# PandaBoard_Shell.net
KiCad netlist of a schematic drawn in EAGLE
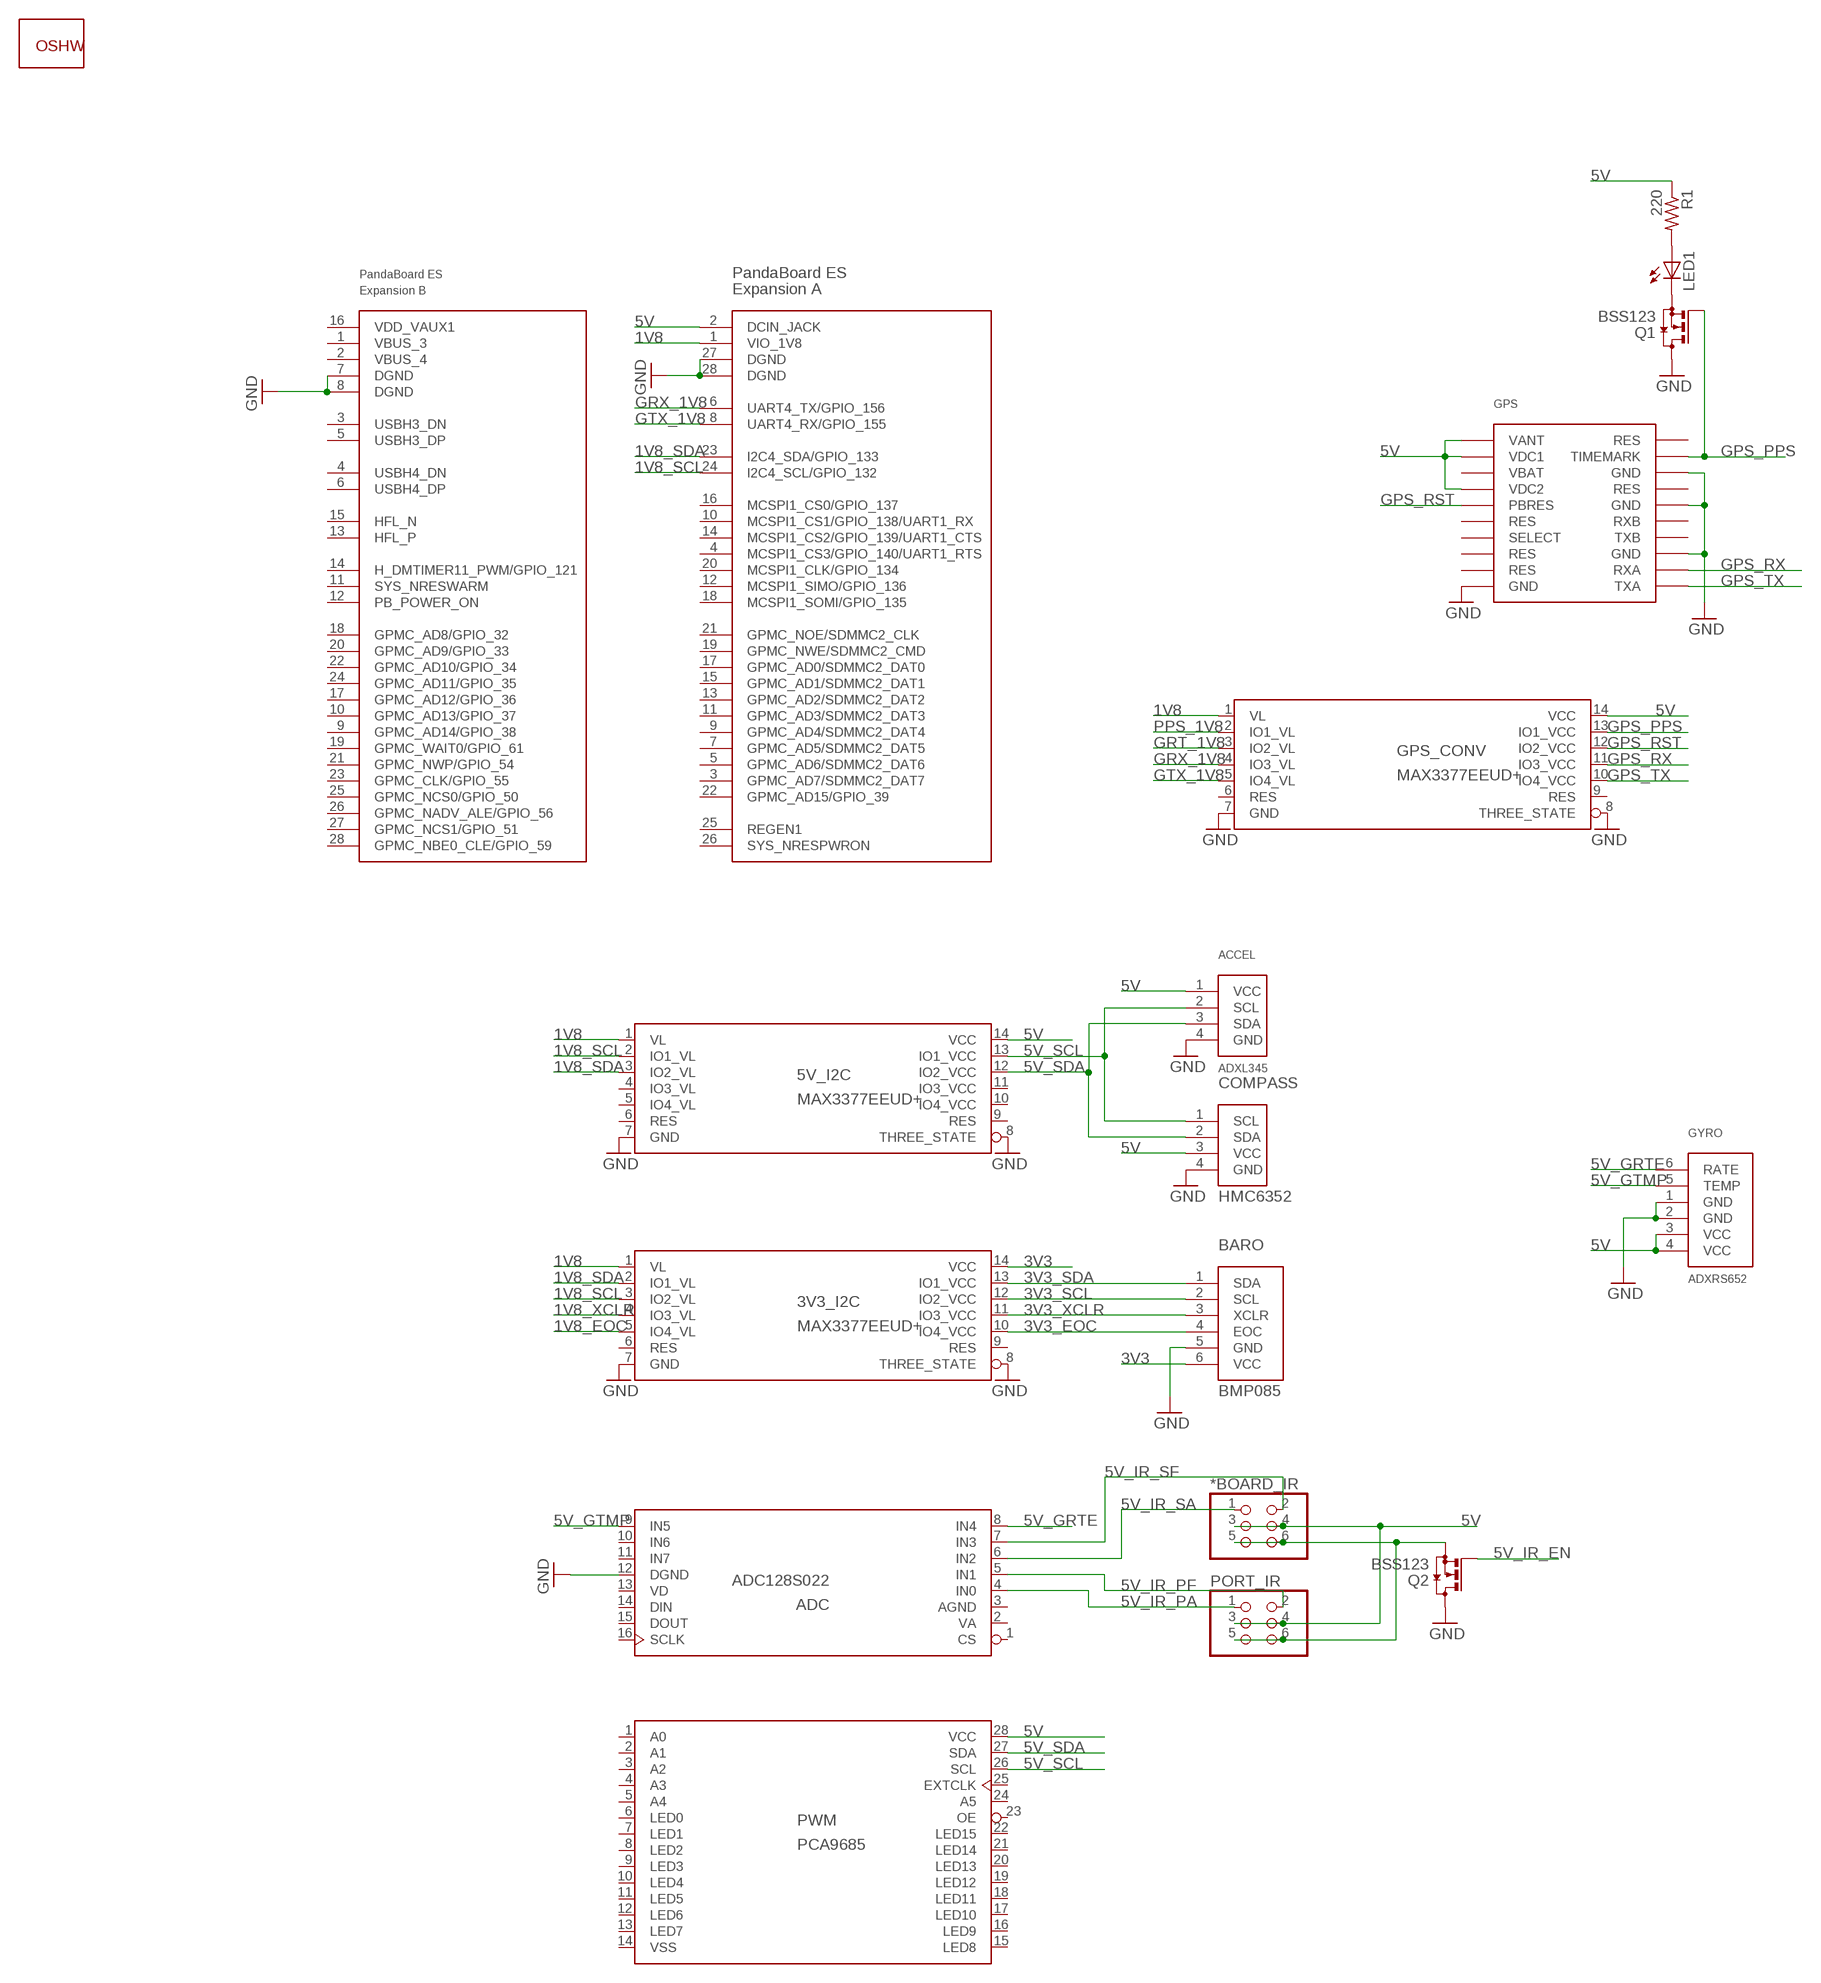
[diagram p0: schematic, sheet 1]

(export (version "E")
  (design (tool "Eeschema 10.0.6"))
  (components
    (comp (ref "*BOARD_IR")
      (value "PINHD-2X3")
      (footprint "eagle-import:2X03")
      (libsource (lib "eagle-import") (part "PINHD-2X3"))
    )
    (comp (ref "3V3_I2C")
      (value "MAX3377EEUD+")
      (footprint "eagle-import:MAX3377EEUD+")
      (libsource (lib "eagle-import") (part "MAX3377EEUD+"))
    )
    (comp (ref "5V_I2C")
      (value "MAX3377EEUD+")
      (footprint "eagle-import:MAX3377EEUD+")
      (libsource (lib "eagle-import") (part "MAX3377EEUD+"))
    )
    (comp (ref "ACCEL")
      (value "ADXL345")
      (footprint "eagle-import:ADXL345")
      (libsource (lib "eagle-import") (part "ADXL345"))
    )
    (comp (ref "ADC")
      (value "ADC128S022")
      (footprint "eagle-import:ADC128S022")
      (libsource (lib "eagle-import") (part "ADC128S022"))
    )
    (comp (ref "BARO")
      (value "BMP085")
      (footprint "eagle-import:6-PIN_0.1_")
      (libsource (lib "eagle-import") (part "BMP085"))
    )
    (comp (ref "COMPASS")
      (value "HMC6352")
      (footprint "eagle-import:HMC6352")
      (libsource (lib "eagle-import") (part "HMC6352"))
    )
    (comp (ref "GOLD_ORB_SM1")
      (value "OSHWLOGO_GOLD_ORB_SM")
      (footprint "eagle-import:OSHW2")
      (libsource (lib "eagle-import") (part "OSHWLOGO_GOLD_ORB_SM"))
    )
    (comp (ref "GPS")
      (value "ET-102_V2.0")
      (footprint "eagle-import:10X2_HEADER")
      (libsource (lib "eagle-import") (part "ET-102_V2.0"))
    )
    (comp (ref "GPS_CONV")
      (value "MAX3377EEUD+")
      (footprint "eagle-import:MAX3377EEUD+")
      (libsource (lib "eagle-import") (part "MAX3377EEUD+"))
    )
    (comp (ref "GYRO")
      (value "ADXRS652")
      (footprint "eagle-import:ADXRS652")
      (libsource (lib "eagle-import") (part "ADXRS652"))
    )
    (comp (ref "LED1")
      (value "LEDCHIPLED_0805")
      (footprint "eagle-import:CHIPLED_0805")
      (libsource (lib "eagle-import") (part "LEDCHIPLED_0805"))
    )
    (comp (ref "PORT_IR")
      (value "PINHD-2X3")
      (footprint "eagle-import:2X03")
      (libsource (lib "eagle-import") (part "PINHD-2X3"))
    )
    (comp (ref "PWM")
      (value "PCA9685")
      (footprint "eagle-import:PCA9685")
      (libsource (lib "eagle-import") (part "PCA9685"))
    )
    (comp (ref "Q1")
      (value "BSS123")
      (footprint "eagle-import:SOT23")
      (libsource (lib "eagle-import") (part "BSS123"))
    )
    (comp (ref "Q2")
      (value "BSS123")
      (footprint "eagle-import:SOT23")
      (libsource (lib "eagle-import") (part "BSS123"))
    )
    (comp (ref "R1")
      (value "220")
      (footprint "eagle-import:R0603")
      (libsource (lib "eagle-import") (part "R-US_R0603"))
    )
    (comp (ref "U$1")
      (value "PES_EXP_A")
      (footprint "eagle-import:28-PIN_0.1_")
      (libsource (lib "eagle-import") (part "PES_EXP_A"))
    )
    (comp (ref "U$2")
      (value "PES_EXP_B")
      (footprint "eagle-import:28-PIN_0.1_")
      (libsource (lib "eagle-import") (part "PES_EXP_B"))
    )
  )
  (nets
    (net (code "1") (name "/1V8") (class "Default")
      (node (ref "3V3_I2C") (pin "1") (pinfunction "VL_1") (pintype "power_in"))
      (node (ref "5V_I2C") (pin "1") (pinfunction "VL_1") (pintype "power_in"))
      (node (ref "GPS_CONV") (pin "1") (pinfunction "VL_1") (pintype "power_in"))
      (node (ref "U$1") (pin "1") (pinfunction "VIO_1V8_1") (pintype "bidirectional"))
    )
    (net (code "2") (name "/1V8_EOC") (class "Default")
      (node (ref "3V3_I2C") (pin "5") (pinfunction "IO4_VL_5") (pintype "bidirectional"))
    )
    (net (code "3") (name "/1V8_SCL") (class "Default")
      (node (ref "3V3_I2C") (pin "3") (pinfunction "IO2_VL_3") (pintype "bidirectional"))
      (node (ref "5V_I2C") (pin "2") (pinfunction "IO1_VL_2") (pintype "bidirectional"))
      (node (ref "U$1") (pin "24") (pinfunction "I2C4_SCL/GPIO_132_24") (pintype "bidirectional"))
    )
    (net (code "4") (name "/1V8_SDA") (class "Default")
      (node (ref "3V3_I2C") (pin "2") (pinfunction "IO1_VL_2") (pintype "bidirectional"))
      (node (ref "5V_I2C") (pin "3") (pinfunction "IO2_VL_3") (pintype "bidirectional"))
      (node (ref "U$1") (pin "23") (pinfunction "I2C4_SDA/GPIO_133_23") (pintype "bidirectional"))
    )
    (net (code "5") (name "/1V8_XCLR") (class "Default")
      (node (ref "3V3_I2C") (pin "4") (pinfunction "IO3_VL_4") (pintype "bidirectional"))
    )
    (net (code "6") (name "/3V3") (class "Default")
      (node (ref "3V3_I2C") (pin "14") (pinfunction "VCC_14") (pintype "power_in"))
      (node (ref "BARO") (pin "6") (pinfunction "VCC_6") (pintype "bidirectional"))
    )
    (net (code "7") (name "/3V3_EOC") (class "Default")
      (node (ref "3V3_I2C") (pin "10") (pinfunction "IO4_VCC_10") (pintype "bidirectional"))
      (node (ref "BARO") (pin "4") (pinfunction "EOC_4") (pintype "bidirectional"))
    )
    (net (code "8") (name "/3V3_SCL") (class "Default")
      (node (ref "3V3_I2C") (pin "12") (pinfunction "IO2_VCC_12") (pintype "bidirectional"))
      (node (ref "BARO") (pin "2") (pinfunction "SCL_2") (pintype "bidirectional"))
    )
    (net (code "9") (name "/3V3_SDA") (class "Default")
      (node (ref "3V3_I2C") (pin "13") (pinfunction "IO1_VCC_13") (pintype "bidirectional"))
      (node (ref "BARO") (pin "1") (pinfunction "SDA_1") (pintype "bidirectional"))
    )
    (net (code "10") (name "/3V3_XCLR") (class "Default")
      (node (ref "3V3_I2C") (pin "11") (pinfunction "IO3_VCC_11") (pintype "bidirectional"))
      (node (ref "BARO") (pin "3") (pinfunction "XCLR_3") (pintype "bidirectional"))
    )
    (net (code "11") (name "/5V") (class "Default")
      (node (ref "*BOARD_IR") (pin "3") (pinfunction "3_3") (pintype "passive"))
      (node (ref "*BOARD_IR") (pin "4") (pinfunction "4_4") (pintype "passive"))
      (node (ref "5V_I2C") (pin "14") (pinfunction "VCC_14") (pintype "power_in"))
      (node (ref "ACCEL") (pin "1") (pinfunction "VCC_1") (pintype "bidirectional"))
      (node (ref "COMPASS") (pin "3") (pinfunction "VCC_3") (pintype "bidirectional"))
      (node (ref "GPS") (pin "P$1") (pinfunction "VANT_P$1") (pintype "power_in"))
      (node (ref "GPS") (pin "P$2") (pinfunction "VDC1_P$2") (pintype "power_in"))
      (node (ref "GPS") (pin "P$4") (pinfunction "VDC2_P$4") (pintype "power_in"))
      (node (ref "GPS_CONV") (pin "14") (pinfunction "VCC_14") (pintype "power_in"))
      (node (ref "GYRO") (pin "3") (pinfunction "VCC_3") (pintype "bidirectional"))
      (node (ref "GYRO") (pin "4") (pinfunction "VCC_4") (pintype "bidirectional"))
      (node (ref "PORT_IR") (pin "3") (pinfunction "3_3") (pintype "passive"))
      (node (ref "PORT_IR") (pin "4") (pinfunction "4_4") (pintype "passive"))
      (node (ref "PWM") (pin "28") (pinfunction "VCC_28") (pintype "power_in"))
      (node (ref "R1") (pin "1") (pinfunction "1_1") (pintype "passive"))
      (node (ref "U$1") (pin "2") (pinfunction "DCIN_JACK_2") (pintype "bidirectional"))
    )
    (net (code "12") (name "/5V_GRTE") (class "Default")
      (node (ref "ADC") (pin "8") (pinfunction "IN4_8") (pintype "input"))
      (node (ref "GYRO") (pin "6") (pinfunction "RATE_6") (pintype "bidirectional"))
    )
    (net (code "13") (name "/5V_GTMP") (class "Default")
      (node (ref "ADC") (pin "9") (pinfunction "IN5_9") (pintype "input"))
      (node (ref "GYRO") (pin "5") (pinfunction "TEMP_5") (pintype "bidirectional"))
    )
    (net (code "14") (name "/5V_IR_EN") (class "Default")
      (node (ref "Q2") (pin "1") (pinfunction "G_1") (pintype "passive"))
    )
    (net (code "15") (name "/5V_IR_PA") (class "Default")
      (node (ref "ADC") (pin "4") (pinfunction "IN0_4") (pintype "input"))
      (node (ref "PORT_IR") (pin "1") (pinfunction "1_1") (pintype "passive"))
    )
    (net (code "16") (name "/5V_IR_PF") (class "Default")
      (node (ref "ADC") (pin "5") (pinfunction "IN1_5") (pintype "input"))
      (node (ref "PORT_IR") (pin "2") (pinfunction "2_2") (pintype "passive"))
    )
    (net (code "17") (name "/5V_IR_SA") (class "Default")
      (node (ref "*BOARD_IR") (pin "1") (pinfunction "1_1") (pintype "passive"))
      (node (ref "ADC") (pin "6") (pinfunction "IN2_6") (pintype "input"))
    )
    (net (code "18") (name "/5V_IR_SF") (class "Default")
      (node (ref "*BOARD_IR") (pin "2") (pinfunction "2_2") (pintype "passive"))
      (node (ref "ADC") (pin "7") (pinfunction "IN3_7") (pintype "input"))
    )
    (net (code "19") (name "/5V_SCL") (class "Default")
      (node (ref "5V_I2C") (pin "13") (pinfunction "IO1_VCC_13") (pintype "bidirectional"))
      (node (ref "ACCEL") (pin "2") (pinfunction "SCL_2") (pintype "bidirectional"))
      (node (ref "COMPASS") (pin "1") (pinfunction "SCL_1") (pintype "bidirectional"))
      (node (ref "PWM") (pin "26") (pinfunction "SCL_26") (pintype "bidirectional"))
    )
    (net (code "20") (name "/5V_SDA") (class "Default")
      (node (ref "5V_I2C") (pin "12") (pinfunction "IO2_VCC_12") (pintype "bidirectional"))
      (node (ref "ACCEL") (pin "3") (pinfunction "SDA_3") (pintype "bidirectional"))
      (node (ref "COMPASS") (pin "2") (pinfunction "SDA_2") (pintype "bidirectional"))
      (node (ref "PWM") (pin "27") (pinfunction "SDA_27") (pintype "bidirectional"))
    )
    (net (code "21") (name "/AGND") (class "Default")
      (node (ref "ADC") (pin "3") (pinfunction "AGND_3") (pintype "power_in"))
    )
    (net (code "22") (name "/GPS_PPS") (class "Default")
      (node (ref "GPS") (pin "P$19") (pinfunction "TIMEMARK_P$19") (pintype "output"))
      (node (ref "GPS_CONV") (pin "13") (pinfunction "IO1_VCC_13") (pintype "bidirectional"))
      (node (ref "Q1") (pin "1") (pinfunction "G_1") (pintype "passive"))
    )
    (net (code "23") (name "/GPS_RST") (class "Default")
      (node (ref "GPS") (pin "P$5") (pinfunction "PBRES_P$5") (pintype "input"))
      (node (ref "GPS_CONV") (pin "12") (pinfunction "IO2_VCC_12") (pintype "bidirectional"))
    )
    (net (code "24") (name "/GPS_RX") (class "Default")
      (node (ref "GPS") (pin "P$12") (pinfunction "RXA_P$12") (pintype "input"))
      (node (ref "GPS_CONV") (pin "11") (pinfunction "IO3_VCC_11") (pintype "bidirectional"))
    )
    (net (code "25") (name "/GPS_TX") (class "Default")
      (node (ref "GPS") (pin "P$11") (pinfunction "TXA_P$11") (pintype "output"))
      (node (ref "GPS_CONV") (pin "10") (pinfunction "IO4_VCC_10") (pintype "bidirectional"))
    )
    (net (code "26") (name "/GRT_1V8") (class "Default")
      (node (ref "GPS_CONV") (pin "3") (pinfunction "IO2_VL_3") (pintype "bidirectional"))
    )
    (net (code "27") (name "/GRX_1V8") (class "Default")
      (node (ref "GPS_CONV") (pin "4") (pinfunction "IO3_VL_4") (pintype "bidirectional"))
      (node (ref "U$1") (pin "6") (pinfunction "UART4_TX/GPIO_156_6") (pintype "bidirectional"))
    )
    (net (code "28") (name "/GTX_1V8") (class "Default")
      (node (ref "GPS_CONV") (pin "5") (pinfunction "IO4_VL_5") (pintype "bidirectional"))
      (node (ref "U$1") (pin "8") (pinfunction "UART4_RX/GPIO_155_8") (pintype "bidirectional"))
    )
    (net (code "29") (name "/PPS_1V8") (class "Default")
      (node (ref "GPS_CONV") (pin "2") (pinfunction "IO1_VL_2") (pintype "bidirectional"))
    )
    (net (code "30") (name "/VA") (class "Default")
      (node (ref "ADC") (pin "2") (pinfunction "VA_2") (pintype "power_in"))
    )
    (net (code "31") (name "/VBAT") (class "Default")
      (node (ref "GPS") (pin "P$3") (pinfunction "VBAT_P$3") (pintype "power_in"))
    )
    (net (code "32") (name "/VD") (class "Default")
      (node (ref "ADC") (pin "13") (pinfunction "VD_13") (pintype "power_in"))
    )
    (net (code "33") (name "/VSS") (class "Default")
      (node (ref "PWM") (pin "14") (pinfunction "VSS_14") (pintype "power_in"))
    )
    (net (code "34") (name "GND") (class "Default")
      (node (ref "3V3_I2C") (pin "7") (pinfunction "GND_7") (pintype "power_in"))
      (node (ref "3V3_I2C") (pin "8") (pinfunction "THREE_STATE_8") (pintype "input"))
      (node (ref "5V_I2C") (pin "7") (pinfunction "GND_7") (pintype "power_in"))
      (node (ref "5V_I2C") (pin "8") (pinfunction "THREE_STATE_8") (pintype "input"))
      (node (ref "ACCEL") (pin "4") (pinfunction "GND_4") (pintype "bidirectional"))
      (node (ref "ADC") (pin "12") (pinfunction "DGND_12") (pintype "power_in"))
      (node (ref "BARO") (pin "5") (pinfunction "GND_5") (pintype "bidirectional"))
      (node (ref "COMPASS") (pin "4") (pinfunction "GND_4") (pintype "bidirectional"))
      (node (ref "GPS") (pin "P$10") (pinfunction "GND_P$10") (pintype "power_in"))
      (node (ref "GPS") (pin "P$13") (pinfunction "GND_P$13") (pintype "power_in"))
      (node (ref "GPS") (pin "P$16") (pinfunction "GND_P$16") (pintype "power_in"))
      (node (ref "GPS") (pin "P$18") (pinfunction "GND_P$18") (pintype "power_in"))
      (node (ref "GPS_CONV") (pin "7") (pinfunction "GND_7") (pintype "power_in"))
      (node (ref "GPS_CONV") (pin "8") (pinfunction "THREE_STATE_8") (pintype "input"))
      (node (ref "GYRO") (pin "1") (pinfunction "GND_1") (pintype "bidirectional"))
      (node (ref "GYRO") (pin "2") (pinfunction "GND_2") (pintype "bidirectional"))
      (node (ref "Q1") (pin "3") (pinfunction "D_3") (pintype "passive"))
      (node (ref "Q2") (pin "3") (pinfunction "D_3") (pintype "passive"))
      (node (ref "U$1") (pin "27") (pinfunction "DGND_27") (pintype "bidirectional"))
      (node (ref "U$1") (pin "28") (pinfunction "DGND_28") (pintype "bidirectional"))
      (node (ref "U$2") (pin "7") (pinfunction "DGND_7") (pintype "bidirectional"))
      (node (ref "U$2") (pin "8") (pinfunction "DGND_8") (pintype "bidirectional"))
    )
    (net (code "35") (name "Net-(LED1-PadA)") (class "Default")
      (node (ref "LED1") (pin "A") (pinfunction "A_A") (pintype "passive"))
      (node (ref "R1") (pin "2") (pinfunction "2_2") (pintype "passive"))
    )
    (net (code "36") (name "Net-(Q1-S)") (class "Default")
      (node (ref "LED1") (pin "C") (pinfunction "C_C") (pintype "passive"))
      (node (ref "Q1") (pin "2") (pinfunction "S_2") (pintype "passive"))
    )
    (net (code "37") (name "Net-(Q2-S)") (class "Default")
      (node (ref "*BOARD_IR") (pin "5") (pinfunction "5_5") (pintype "passive"))
      (node (ref "*BOARD_IR") (pin "6") (pinfunction "6_6") (pintype "passive"))
      (node (ref "PORT_IR") (pin "5") (pinfunction "5_5") (pintype "passive"))
      (node (ref "PORT_IR") (pin "6") (pinfunction "6_6") (pintype "passive"))
      (node (ref "Q2") (pin "2") (pinfunction "S_2") (pintype "passive"))
    )
    (net (code "38") (name "unconnected-(3V3_I2C-RES-Pad6)") (class "Default")
      (node (ref "3V3_I2C") (pin "6") (pinfunction "RES_6") (pintype "no_connect"))
    )
    (net (code "39") (name "unconnected-(3V3_I2C-RES-Pad9)") (class "Default")
      (node (ref "3V3_I2C") (pin "9") (pinfunction "RES_9") (pintype "no_connect"))
    )
    (net (code "40") (name "unconnected-(5V_I2C-IO3_VCC-Pad11)") (class "Default")
      (node (ref "5V_I2C") (pin "11") (pinfunction "IO3_VCC_11") (pintype "bidirectional"))
    )
    (net (code "41") (name "unconnected-(5V_I2C-IO3_VL-Pad4)") (class "Default")
      (node (ref "5V_I2C") (pin "4") (pinfunction "IO3_VL_4") (pintype "bidirectional"))
    )
    (net (code "42") (name "unconnected-(5V_I2C-IO4_VCC-Pad10)") (class "Default")
      (node (ref "5V_I2C") (pin "10") (pinfunction "IO4_VCC_10") (pintype "bidirectional"))
    )
    (net (code "43") (name "unconnected-(5V_I2C-IO4_VL-Pad5)") (class "Default")
      (node (ref "5V_I2C") (pin "5") (pinfunction "IO4_VL_5") (pintype "bidirectional"))
    )
    (net (code "44") (name "unconnected-(5V_I2C-RES-Pad6)") (class "Default")
      (node (ref "5V_I2C") (pin "6") (pinfunction "RES_6") (pintype "no_connect"))
    )
    (net (code "45") (name "unconnected-(5V_I2C-RES-Pad9)") (class "Default")
      (node (ref "5V_I2C") (pin "9") (pinfunction "RES_9") (pintype "no_connect"))
    )
    (net (code "46") (name "unconnected-(ADC-CS-Pad1)") (class "Default")
      (node (ref "ADC") (pin "1") (pinfunction "CS_1") (pintype "input"))
    )
    (net (code "47") (name "unconnected-(ADC-DIN-Pad14)") (class "Default")
      (node (ref "ADC") (pin "14") (pinfunction "DIN_14") (pintype "bidirectional"))
    )
    (net (code "48") (name "unconnected-(ADC-DOUT-Pad15)") (class "Default")
      (node (ref "ADC") (pin "15") (pinfunction "DOUT_15") (pintype "bidirectional"))
    )
    (net (code "49") (name "unconnected-(ADC-IN6-Pad10)") (class "Default")
      (node (ref "ADC") (pin "10") (pinfunction "IN6_10") (pintype "input"))
    )
    (net (code "50") (name "unconnected-(ADC-IN7-Pad11)") (class "Default")
      (node (ref "ADC") (pin "11") (pinfunction "IN7_11") (pintype "input"))
    )
    (net (code "51") (name "unconnected-(ADC-SCLK-Pad16)") (class "Default")
      (node (ref "ADC") (pin "16") (pinfunction "SCLK_16") (pintype "bidirectional"))
    )
    (net (code "52") (name "unconnected-(GPS-RES-PadP$6)") (class "Default")
      (node (ref "GPS") (pin "P$6") (pinfunction "RES_P$6") (pintype "no_connect"))
    )
    (net (code "53") (name "unconnected-(GPS-RES-PadP$8)") (class "Default")
      (node (ref "GPS") (pin "P$8") (pinfunction "RES_P$8") (pintype "no_connect"))
    )
    (net (code "54") (name "unconnected-(GPS-RES-PadP$9)") (class "Default")
      (node (ref "GPS") (pin "P$9") (pinfunction "RES_P$9") (pintype "no_connect"))
    )
    (net (code "55") (name "unconnected-(GPS-RES-PadP$17)") (class "Default")
      (node (ref "GPS") (pin "P$17") (pinfunction "RES_P$17") (pintype "no_connect"))
    )
    (net (code "56") (name "unconnected-(GPS-RES-PadP$20)") (class "Default")
      (node (ref "GPS") (pin "P$20") (pinfunction "RES_P$20") (pintype "no_connect"))
    )
    (net (code "57") (name "unconnected-(GPS-RXB-PadP$15)") (class "Default")
      (node (ref "GPS") (pin "P$15") (pinfunction "RXB_P$15") (pintype "input"))
    )
    (net (code "58") (name "unconnected-(GPS-SELECT-PadP$7)") (class "Default")
      (node (ref "GPS") (pin "P$7") (pinfunction "SELECT_P$7") (pintype "no_connect"))
    )
    (net (code "59") (name "unconnected-(GPS-TXB-PadP$14)") (class "Default")
      (node (ref "GPS") (pin "P$14") (pinfunction "TXB_P$14") (pintype "output"))
    )
    (net (code "60") (name "unconnected-(GPS_CONV-RES-Pad6)") (class "Default")
      (node (ref "GPS_CONV") (pin "6") (pinfunction "RES_6") (pintype "no_connect"))
    )
    (net (code "61") (name "unconnected-(GPS_CONV-RES-Pad9)") (class "Default")
      (node (ref "GPS_CONV") (pin "9") (pinfunction "RES_9") (pintype "no_connect"))
    )
    (net (code "62") (name "unconnected-(PWM-A0-Pad1)") (class "Default")
      (node (ref "PWM") (pin "1") (pinfunction "A0_1") (pintype "input"))
    )
    (net (code "63") (name "unconnected-(PWM-A1-Pad2)") (class "Default")
      (node (ref "PWM") (pin "2") (pinfunction "A1_2") (pintype "input"))
    )
    (net (code "64") (name "unconnected-(PWM-A2-Pad3)") (class "Default")
      (node (ref "PWM") (pin "3") (pinfunction "A2_3") (pintype "input"))
    )
    (net (code "65") (name "unconnected-(PWM-A3-Pad4)") (class "Default")
      (node (ref "PWM") (pin "4") (pinfunction "A3_4") (pintype "input"))
    )
    (net (code "66") (name "unconnected-(PWM-A4-Pad5)") (class "Default")
      (node (ref "PWM") (pin "5") (pinfunction "A4_5") (pintype "input"))
    )
    (net (code "67") (name "unconnected-(PWM-A5-Pad24)") (class "Default")
      (node (ref "PWM") (pin "24") (pinfunction "A5_24") (pintype "input"))
    )
    (net (code "68") (name "unconnected-(PWM-EXTCLK-Pad25)") (class "Default")
      (node (ref "PWM") (pin "25") (pinfunction "EXTCLK_25") (pintype "input"))
    )
    (net (code "69") (name "unconnected-(PWM-LED0-Pad6)") (class "Default")
      (node (ref "PWM") (pin "6") (pinfunction "LED0_6") (pintype "output"))
    )
    (net (code "70") (name "unconnected-(PWM-LED1-Pad7)") (class "Default")
      (node (ref "PWM") (pin "7") (pinfunction "LED1_7") (pintype "output"))
    )
    (net (code "71") (name "unconnected-(PWM-LED2-Pad8)") (class "Default")
      (node (ref "PWM") (pin "8") (pinfunction "LED2_8") (pintype "output"))
    )
    (net (code "72") (name "unconnected-(PWM-LED3-Pad9)") (class "Default")
      (node (ref "PWM") (pin "9") (pinfunction "LED3_9") (pintype "output"))
    )
    (net (code "73") (name "unconnected-(PWM-LED4-Pad10)") (class "Default")
      (node (ref "PWM") (pin "10") (pinfunction "LED4_10") (pintype "output"))
    )
    (net (code "74") (name "unconnected-(PWM-LED5-Pad11)") (class "Default")
      (node (ref "PWM") (pin "11") (pinfunction "LED5_11") (pintype "output"))
    )
    (net (code "75") (name "unconnected-(PWM-LED6-Pad12)") (class "Default")
      (node (ref "PWM") (pin "12") (pinfunction "LED6_12") (pintype "output"))
    )
    (net (code "76") (name "unconnected-(PWM-LED7-Pad13)") (class "Default")
      (node (ref "PWM") (pin "13") (pinfunction "LED7_13") (pintype "output"))
    )
    (net (code "77") (name "unconnected-(PWM-LED8-Pad15)") (class "Default")
      (node (ref "PWM") (pin "15") (pinfunction "LED8_15") (pintype "output"))
    )
    (net (code "78") (name "unconnected-(PWM-LED9-Pad16)") (class "Default")
      (node (ref "PWM") (pin "16") (pinfunction "LED9_16") (pintype "output"))
    )
    (net (code "79") (name "unconnected-(PWM-LED10-Pad17)") (class "Default")
      (node (ref "PWM") (pin "17") (pinfunction "LED10_17") (pintype "output"))
    )
    (net (code "80") (name "unconnected-(PWM-LED11-Pad18)") (class "Default")
      (node (ref "PWM") (pin "18") (pinfunction "LED11_18") (pintype "output"))
    )
    (net (code "81") (name "unconnected-(PWM-LED12-Pad19)") (class "Default")
      (node (ref "PWM") (pin "19") (pinfunction "LED12_19") (pintype "output"))
    )
    (net (code "82") (name "unconnected-(PWM-LED13-Pad20)") (class "Default")
      (node (ref "PWM") (pin "20") (pinfunction "LED13_20") (pintype "output"))
    )
    (net (code "83") (name "unconnected-(PWM-LED14-Pad21)") (class "Default")
      (node (ref "PWM") (pin "21") (pinfunction "LED14_21") (pintype "output"))
    )
    (net (code "84") (name "unconnected-(PWM-LED15-Pad22)") (class "Default")
      (node (ref "PWM") (pin "22") (pinfunction "LED15_22") (pintype "output"))
    )
    (net (code "85") (name "unconnected-(PWM-OE-Pad23)") (class "Default")
      (node (ref "PWM") (pin "23") (pinfunction "OE_23") (pintype "input"))
    )
    (net (code "86") (name "unconnected-(U$1-GPMC_AD0{slash}SDMMC2_DAT0-Pad17)") (class "Default")
      (node (ref "U$1") (pin "17") (pinfunction "GPMC_AD0/SDMMC2_DAT0_17") (pintype "bidirectional"))
    )
    (net (code "87") (name "unconnected-(U$1-GPMC_AD1{slash}SDMMC2_DAT1-Pad15)") (class "Default")
      (node (ref "U$1") (pin "15") (pinfunction "GPMC_AD1/SDMMC2_DAT1_15") (pintype "bidirectional"))
    )
    (net (code "88") (name "unconnected-(U$1-GPMC_AD2{slash}SDMMC2_DAT2-Pad13)") (class "Default")
      (node (ref "U$1") (pin "13") (pinfunction "GPMC_AD2/SDMMC2_DAT2_13") (pintype "bidirectional"))
    )
    (net (code "89") (name "unconnected-(U$1-GPMC_AD3{slash}SDMMC2_DAT3-Pad11)") (class "Default")
      (node (ref "U$1") (pin "11") (pinfunction "GPMC_AD3/SDMMC2_DAT3_11") (pintype "bidirectional"))
    )
    (net (code "90") (name "unconnected-(U$1-GPMC_AD4{slash}SDMMC2_DAT4-Pad9)") (class "Default")
      (node (ref "U$1") (pin "9") (pinfunction "GPMC_AD4/SDMMC2_DAT4_9") (pintype "bidirectional"))
    )
    (net (code "91") (name "unconnected-(U$1-GPMC_AD5{slash}SDMMC2_DAT5-Pad7)") (class "Default")
      (node (ref "U$1") (pin "7") (pinfunction "GPMC_AD5/SDMMC2_DAT5_7") (pintype "bidirectional"))
    )
    (net (code "92") (name "unconnected-(U$1-GPMC_AD6{slash}SDMMC2_DAT6-Pad5)") (class "Default")
      (node (ref "U$1") (pin "5") (pinfunction "GPMC_AD6/SDMMC2_DAT6_5") (pintype "bidirectional"))
    )
    (net (code "93") (name "unconnected-(U$1-GPMC_AD7{slash}SDMMC2_DAT7-Pad3)") (class "Default")
      (node (ref "U$1") (pin "3") (pinfunction "GPMC_AD7/SDMMC2_DAT7_3") (pintype "bidirectional"))
    )
    (net (code "94") (name "unconnected-(U$1-GPMC_AD15{slash}GPIO_39-Pad22)") (class "Default")
      (node (ref "U$1") (pin "22") (pinfunction "GPMC_AD15/GPIO_39_22") (pintype "bidirectional"))
    )
    (net (code "95") (name "unconnected-(U$1-GPMC_NOE{slash}SDMMC2_CLK-Pad21)") (class "Default")
      (node (ref "U$1") (pin "21") (pinfunction "GPMC_NOE/SDMMC2_CLK_21") (pintype "bidirectional"))
    )
    (net (code "96") (name "unconnected-(U$1-GPMC_NWE{slash}SDMMC2_CMD-Pad19)") (class "Default")
      (node (ref "U$1") (pin "19") (pinfunction "GPMC_NWE/SDMMC2_CMD_19") (pintype "bidirectional"))
    )
    (net (code "97") (name "unconnected-(U$1-MCSPI1_CLK{slash}GPIO_134-Pad20)") (class "Default")
      (node (ref "U$1") (pin "20") (pinfunction "MCSPI1_CLK/GPIO_134_20") (pintype "bidirectional"))
    )
    (net (code "98") (name "unconnected-(U$1-MCSPI1_CS0{slash}GPIO_137-Pad16)") (class "Default")
      (node (ref "U$1") (pin "16") (pinfunction "MCSPI1_CS0/GPIO_137_16") (pintype "bidirectional"))
    )
    (net (code "99") (name "unconnected-(U$1-MCSPI1_CS1{slash}GPIO_138{slash}UART1_RX-Pad10)") (class "Default")
      (node (ref "U$1") (pin "10") (pinfunction "MCSPI1_CS1/GPIO_138/UART1_RX_10") (pintype "bidirectional"))
    )
    (net (code "100") (name "unconnected-(U$1-MCSPI1_CS2{slash}GPIO_139{slash}UART1_CTS-Pad14)") (class "Default")
      (node (ref "U$1") (pin "14") (pinfunction "MCSPI1_CS2/GPIO_139/UART1_CTS_14") (pintype "bidirectional"))
    )
    (net (code "101") (name "unconnected-(U$1-MCSPI1_CS3{slash}GPIO_140{slash}UART1_RTS-Pad4)") (class "Default")
      (node (ref "U$1") (pin "4") (pinfunction "MCSPI1_CS3/GPIO_140/UART1_RTS_4") (pintype "bidirectional"))
    )
    (net (code "102") (name "unconnected-(U$1-MCSPI1_SIMO{slash}GPIO_136-Pad12)") (class "Default")
      (node (ref "U$1") (pin "12") (pinfunction "MCSPI1_SIMO/GPIO_136_12") (pintype "bidirectional"))
    )
    (net (code "103") (name "unconnected-(U$1-MCSPI1_SOMI{slash}GPIO_135-Pad18)") (class "Default")
      (node (ref "U$1") (pin "18") (pinfunction "MCSPI1_SOMI/GPIO_135_18") (pintype "bidirectional"))
    )
    (net (code "104") (name "unconnected-(U$1-REGEN1-Pad25)") (class "Default")
      (node (ref "U$1") (pin "25") (pinfunction "REGEN1_25") (pintype "bidirectional"))
    )
    (net (code "105") (name "unconnected-(U$1-SYS_NRESPWRON-Pad26)") (class "Default")
      (node (ref "U$1") (pin "26") (pinfunction "SYS_NRESPWRON_26") (pintype "bidirectional"))
    )
    (net (code "106") (name "unconnected-(U$2-GPMC_AD8{slash}GPIO_32-Pad18)") (class "Default")
      (node (ref "U$2") (pin "18") (pinfunction "GPMC_AD8/GPIO_32_18") (pintype "bidirectional"))
    )
    (net (code "107") (name "unconnected-(U$2-GPMC_AD9{slash}GPIO_33-Pad20)") (class "Default")
      (node (ref "U$2") (pin "20") (pinfunction "GPMC_AD9/GPIO_33_20") (pintype "bidirectional"))
    )
    (net (code "108") (name "unconnected-(U$2-GPMC_AD10{slash}GPIO_34-Pad22)") (class "Default")
      (node (ref "U$2") (pin "22") (pinfunction "GPMC_AD10/GPIO_34_22") (pintype "bidirectional"))
    )
    (net (code "109") (name "unconnected-(U$2-GPMC_AD11{slash}GPIO_35-Pad24)") (class "Default")
      (node (ref "U$2") (pin "24") (pinfunction "GPMC_AD11/GPIO_35_24") (pintype "bidirectional"))
    )
    (net (code "110") (name "unconnected-(U$2-GPMC_AD12{slash}GPIO_36-Pad17)") (class "Default")
      (node (ref "U$2") (pin "17") (pinfunction "GPMC_AD12/GPIO_36_17") (pintype "bidirectional"))
    )
    (net (code "111") (name "unconnected-(U$2-GPMC_AD13{slash}GPIO_37-Pad10)") (class "Default")
      (node (ref "U$2") (pin "10") (pinfunction "GPMC_AD13/GPIO_37_10") (pintype "bidirectional"))
    )
    (net (code "112") (name "unconnected-(U$2-GPMC_AD14{slash}GPIO_38-Pad9)") (class "Default")
      (node (ref "U$2") (pin "9") (pinfunction "GPMC_AD14/GPIO_38_9") (pintype "bidirectional"))
    )
    (net (code "113") (name "unconnected-(U$2-GPMC_CLK{slash}GPIO_55-Pad23)") (class "Default")
      (node (ref "U$2") (pin "23") (pinfunction "GPMC_CLK/GPIO_55_23") (pintype "bidirectional"))
    )
    (net (code "114") (name "unconnected-(U$2-GPMC_NADV_ALE{slash}GPIO_56-Pad26)") (class "Default")
      (node (ref "U$2") (pin "26") (pinfunction "GPMC_NADV_ALE/GPIO_56_26") (pintype "bidirectional"))
    )
    (net (code "115") (name "unconnected-(U$2-GPMC_NBE0_CLE{slash}GPIO_59-Pad28)") (class "Default")
      (node (ref "U$2") (pin "28") (pinfunction "GPMC_NBE0_CLE/GPIO_59_28") (pintype "bidirectional"))
    )
    (net (code "116") (name "unconnected-(U$2-GPMC_NCS0{slash}GPIO_50-Pad25)") (class "Default")
      (node (ref "U$2") (pin "25") (pinfunction "GPMC_NCS0/GPIO_50_25") (pintype "bidirectional"))
    )
    (net (code "117") (name "unconnected-(U$2-GPMC_NCS1{slash}GPIO_51-Pad27)") (class "Default")
      (node (ref "U$2") (pin "27") (pinfunction "GPMC_NCS1/GPIO_51_27") (pintype "bidirectional"))
    )
    (net (code "118") (name "unconnected-(U$2-GPMC_NWP{slash}GPIO_54-Pad21)") (class "Default")
      (node (ref "U$2") (pin "21") (pinfunction "GPMC_NWP/GPIO_54_21") (pintype "bidirectional"))
    )
    (net (code "119") (name "unconnected-(U$2-GPMC_WAIT0{slash}GPIO_61-Pad19)") (class "Default")
      (node (ref "U$2") (pin "19") (pinfunction "GPMC_WAIT0/GPIO_61_19") (pintype "bidirectional"))
    )
    (net (code "120") (name "unconnected-(U$2-HFL_N-Pad15)") (class "Default")
      (node (ref "U$2") (pin "15") (pinfunction "HFL_N_15") (pintype "bidirectional"))
    )
    (net (code "121") (name "unconnected-(U$2-HFL_P-Pad13)") (class "Default")
      (node (ref "U$2") (pin "13") (pinfunction "HFL_P_13") (pintype "bidirectional"))
    )
    (net (code "122") (name "unconnected-(U$2-H_DMTIMER11_PWM{slash}GPIO_121-Pad14)") (class "Default")
      (node (ref "U$2") (pin "14") (pinfunction "H_DMTIMER11_PWM/GPIO_121_14") (pintype "bidirectional"))
    )
    (net (code "123") (name "unconnected-(U$2-PB_POWER_ON-Pad12)") (class "Default")
      (node (ref "U$2") (pin "12") (pinfunction "PB_POWER_ON_12") (pintype "bidirectional"))
    )
    (net (code "124") (name "unconnected-(U$2-SYS_NRESWARM-Pad11)") (class "Default")
      (node (ref "U$2") (pin "11") (pinfunction "SYS_NRESWARM_11") (pintype "bidirectional"))
    )
    (net (code "125") (name "unconnected-(U$2-USBH3_DN-Pad3)") (class "Default")
      (node (ref "U$2") (pin "3") (pinfunction "USBH3_DN_3") (pintype "bidirectional"))
    )
    (net (code "126") (name "unconnected-(U$2-USBH3_DP-Pad5)") (class "Default")
      (node (ref "U$2") (pin "5") (pinfunction "USBH3_DP_5") (pintype "bidirectional"))
    )
    (net (code "127") (name "unconnected-(U$2-USBH4_DN-Pad4)") (class "Default")
      (node (ref "U$2") (pin "4") (pinfunction "USBH4_DN_4") (pintype "bidirectional"))
    )
    (net (code "128") (name "unconnected-(U$2-USBH4_DP-Pad6)") (class "Default")
      (node (ref "U$2") (pin "6") (pinfunction "USBH4_DP_6") (pintype "bidirectional"))
    )
    (net (code "129") (name "unconnected-(U$2-VBUS_3-Pad1)") (class "Default")
      (node (ref "U$2") (pin "1") (pinfunction "VBUS_3_1") (pintype "bidirectional"))
    )
    (net (code "130") (name "unconnected-(U$2-VBUS_4-Pad2)") (class "Default")
      (node (ref "U$2") (pin "2") (pinfunction "VBUS_4_2") (pintype "bidirectional"))
    )
    (net (code "131") (name "unconnected-(U$2-VDD_VAUX1-Pad16)") (class "Default")
      (node (ref "U$2") (pin "16") (pinfunction "VDD_VAUX1_16") (pintype "bidirectional"))
    )
  )
)
